# Sheet1.net
KiCad netlist of a schematic drawn in Altium Designer
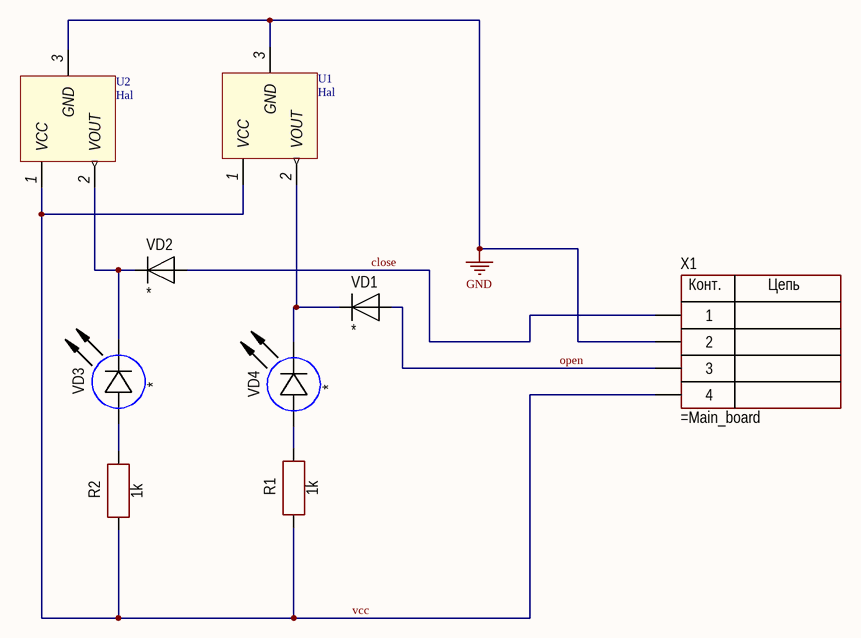
[diagram p0: Sheet1.SchDoc]

(export (version "E")
  (design (tool "Eeschema 10.0.6"))
  (components
    (comp (ref "R1")
      (value "1k")
      (footprint "standard:CH0805R")
      (libsource (lib "Discrete") (part "Resistor"))
    )
    (comp (ref "R2")
      (value "1k")
      (footprint "standard:CH0805R")
      (libsource (lib "Discrete") (part "Resistor"))
    )
    (comp (ref "U1")
      (value "Hal")
      (footprint "A1103ELHLT-T")
      (libsource (lib "Integrated_Library") (part "Hal"))
    )
    (comp (ref "U2")
      (value "Hal")
      (footprint "A1103ELHLT-T")
      (libsource (lib "Integrated_Library") (part "Hal"))
    )
    (comp (ref "VD1") (value "*") (footprint "SOD123") (libsource (lib "Diods") (part "Diod")))
    (comp (ref "VD2") (value "*") (footprint "SOD123") (libsource (lib "Diods") (part "Diod")))
    (comp (ref "VD3") (value "*") (footprint "standard:CH0805LB") (libsource (lib "Discrete") (part "LED")))
    (comp (ref "VD4") (value "*") (footprint "Discrete:CH0805LR") (libsource (lib "Discrete") (part "LED")))
    (comp (ref "X1")
      (value "~")
      (footprint "CON: PLS-4(90)")
      (libsource (lib "Connectors") (part "4-Connector"))
    )
  )
  (nets
    (net (code "1") (name "/close") (class "Default")
      (node (ref "VD2") (pin "1") (pinfunction "1_1") (pintype "passive"))
      (node (ref "X1") (pin "1") (pinfunction "1_1") (pintype "passive"))
    )
    (net (code "2") (name "/open") (class "Default")
      (node (ref "VD1") (pin "1") (pinfunction "1_1") (pintype "passive"))
      (node (ref "X1") (pin "3") (pinfunction "3_3") (pintype "power_in"))
    )
    (net (code "3") (name "/vcc") (class "Default")
      (node (ref "R1") (pin "1") (pinfunction "1_1") (pintype "passive"))
      (node (ref "R2") (pin "1") (pinfunction "1_1") (pintype "passive"))
      (node (ref "U1") (pin "1") (pinfunction "VCC_1") (pintype "power_in"))
      (node (ref "U2") (pin "1") (pinfunction "VCC_1") (pintype "power_in"))
      (node (ref "X1") (pin "4") (pinfunction "4_4") (pintype "power_in"))
    )
    (net (code "4") (name "GND") (class "Default")
      (node (ref "U1") (pin "3") (pinfunction "GND_3") (pintype "power_in"))
      (node (ref "U2") (pin "3") (pinfunction "GND_3") (pintype "power_in"))
      (node (ref "X1") (pin "2") (pinfunction "2_2") (pintype "passive"))
    )
    (net (code "5") (name "Net-(U1-VOUT)") (class "Default")
      (node (ref "U1") (pin "2") (pinfunction "VOUT_2") (pintype "output"))
      (node (ref "VD1") (pin "2") (pinfunction "2_2") (pintype "passive"))
      (node (ref "VD4") (pin "2") (pinfunction "C_2") (pintype "passive"))
    )
    (net (code "6") (name "Net-(U2-VOUT)") (class "Default")
      (node (ref "U2") (pin "2") (pinfunction "VOUT_2") (pintype "output"))
      (node (ref "VD2") (pin "2") (pinfunction "2_2") (pintype "passive"))
      (node (ref "VD3") (pin "2") (pinfunction "C_2") (pintype "passive"))
    )
    (net (code "7") (name "Net-(VD3-A)") (class "Default")
      (node (ref "R2") (pin "2") (pinfunction "2_2") (pintype "passive"))
      (node (ref "VD3") (pin "1") (pinfunction "A_1") (pintype "passive"))
    )
    (net (code "8") (name "Net-(VD4-A)") (class "Default")
      (node (ref "R1") (pin "2") (pinfunction "2_2") (pintype "passive"))
      (node (ref "VD4") (pin "1") (pinfunction "A_1") (pintype "passive"))
    )
  )
)
